# KNX_POE.net
KiCad netlist of a schematic drawn in Altium Designer
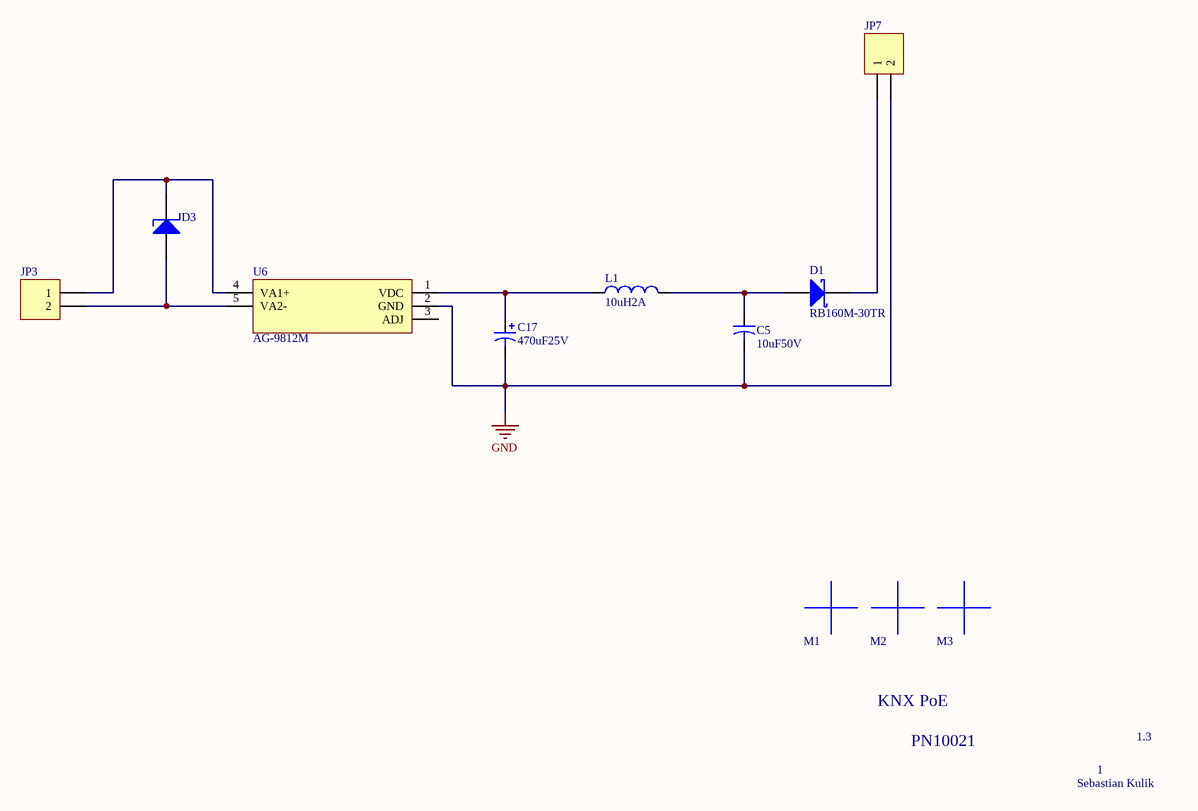
[diagram p0: KNX_POE.SchDoc]

(export (version "E")
  (design (tool "Eeschema 10.0.6"))
  (components
    (comp (ref "C5")
      (value "10uF50V")
      (footprint "C1210")
      (description "AVX,  X7R, 10%, 50V")
      (fields
        (field (name "MANUFACTURER") "AVX")
        (field (name "Comment") "10uF50V_1210")
        (field (name "PUBLISHER") "Sebastian Kulik")
      )
      (libsource (lib "Capacitors") (part "10uF50V_1210"))
    )
    (comp (ref "C17")
      (value "470uF25V")
      (footprint "Panasonic-FT-F_Case")
      (description "Panasonic, FT series")
      (fields
        (field (name "MANUFACTURER") "Panasonic")
        (field (name "Comment") "470uF25V_POL_FT")
        (field (name "PUBLISHER") "Sebastian Kulik")
      )
      (libsource (lib "Capacitors") (part "470uF25V_POL_FT"))
    )
    (comp (ref "D1")
      (value "RB160M-30TR")
      (footprint "SOD123")
      (description "Diode Schottky,2A,40V")
      (fields (field (name "MANUFACTURER") "Rohm") (field (name "PUBLISHER") "Sebastian Kulik"))
      (libsource (lib "Discrete") (part "RB160M-30TR"))
    )
    (comp (ref "D3")
      (value "SMAJ58A-E3/61")
      (footprint "DO214A")
      (description "TVS, 400W, 58V")
      (fields (field (name "MANUFACTURER") "Vishay") (field (name "PUBLISHER") "Sebastian Kulik"))
      (libsource (lib "Discrete") (part "SMAJ58A-E3/61"))
    )
    (comp (ref "JP3")
      (value "Plug_2_90_2.54")
      (footprint "HDR1X2-down")
      (description "Plug, 2-Pin")
      (fields (field (name "MANUFACTURER") "WE") (field (name "PUBLISHER") "Sebastian Kulik"))
      (libsource (lib "Connectors") (part "Plug_2_90_2.54"))
    )
    (comp (ref "JP7")
      (value "Plug_2_90_2.54")
      (footprint "HDR1X2-down")
      (description "Plug, 2-Pin")
      (fields (field (name "MANUFACTURER") "WE") (field (name "PUBLISHER") "Sebastian Kulik"))
      (libsource (lib "") (part "Plug_2_90_2.54_1"))
    )
    (comp (ref "L1")
      (value "10uH2A")
      (footprint "WE-PD2_1")
      (description "WE-PD2, 10uH2A")
      (fields (field (name "MANUFACTURER") "WE") (field (name "PUBLISHER") "Sebastian Kulik"))
      (libsource (lib "Passives") (part "10uH2A_WE-PD2"))
    )
    (comp (ref "M1")
      (value "Paste Mark")
      (footprint "Symbols:Mark-3mm")
      (libsource (lib "Symbols") (part "Mark"))
    )
    (comp (ref "M2")
      (value "Paste Mark")
      (footprint "Symbols:Mark-3mm")
      (libsource (lib "Symbols") (part "Mark"))
    )
    (comp (ref "M3")
      (value "Paste Mark")
      (footprint "Symbols:Mark-3mm")
      (libsource (lib "Symbols") (part "Mark"))
    )
    (comp (ref "U6")
      (value "AG-9812M")
      (footprint "Ag9812M")
      (description "PoE, 12V")
      (fields (field (name "MANUFACTURER") "Silvertel") (field (name "PUBLISHER") "Sebastian Kulik"))
      (libsource (lib "ICs") (part "AG-9812M"))
    )
  )
  (nets
    (net (code "1") (name "GND") (class "Default")
      (node (ref "C17") (pin "2") (pinfunction "2_2") (pintype "passive"))
      (node (ref "C5") (pin "2") (pinfunction "2_2") (pintype "passive"))
      (node (ref "JP7") (pin "2") (pinfunction "2_2") (pintype "passive"))
      (node (ref "U6") (pin "2") (pinfunction "GND_2") (pintype "passive"))
    )
    (net (code "2") (name "Net-(D1-A)") (class "Default")
      (node (ref "C5") (pin "1") (pinfunction "1_1") (pintype "passive"))
      (node (ref "D1") (pin "2") (pinfunction "A_2") (pintype "passive"))
      (node (ref "L1") (pin "2") (pinfunction "2_2") (pintype "passive"))
    )
    (net (code "3") (name "Net-(D1-K)") (class "Default")
      (node (ref "D1") (pin "1") (pinfunction "K_1") (pintype "passive"))
      (node (ref "JP7") (pin "1") (pinfunction "1_1") (pintype "passive"))
    )
    (net (code "4") (name "Net-(D3-A)") (class "Default")
      (node (ref "D3") (pin "2") (pinfunction "A_2") (pintype "passive"))
      (node (ref "JP3") (pin "2") (pinfunction "2_2") (pintype "passive"))
      (node (ref "U6") (pin "5") (pinfunction "VA2-_5") (pintype "passive"))
    )
    (net (code "5") (name "Net-(D3-K)") (class "Default")
      (node (ref "D3") (pin "1") (pinfunction "K_1") (pintype "passive"))
      (node (ref "JP3") (pin "1") (pinfunction "1_1") (pintype "passive"))
      (node (ref "U6") (pin "4") (pinfunction "VA1+_4") (pintype "passive"))
    )
    (net (code "6") (name "Net-(U6-VDC)") (class "Default")
      (node (ref "C17") (pin "1") (pinfunction "1_1") (pintype "passive"))
      (node (ref "L1") (pin "1") (pinfunction "1_1") (pintype "passive"))
      (node (ref "U6") (pin "1") (pinfunction "VDC_1") (pintype "power_in"))
    )
    (net (code "7") (name "unconnected-(U6-ADJ-Pad3)") (class "Default")
      (node (ref "U6") (pin "3") (pinfunction "ADJ_3") (pintype "passive"))
    )
  )
)
